# Adafruit_LC709203F_LiPoly_LiIon_Fuel_Gau.net
KiCad netlist of a schematic drawn in EAGLE
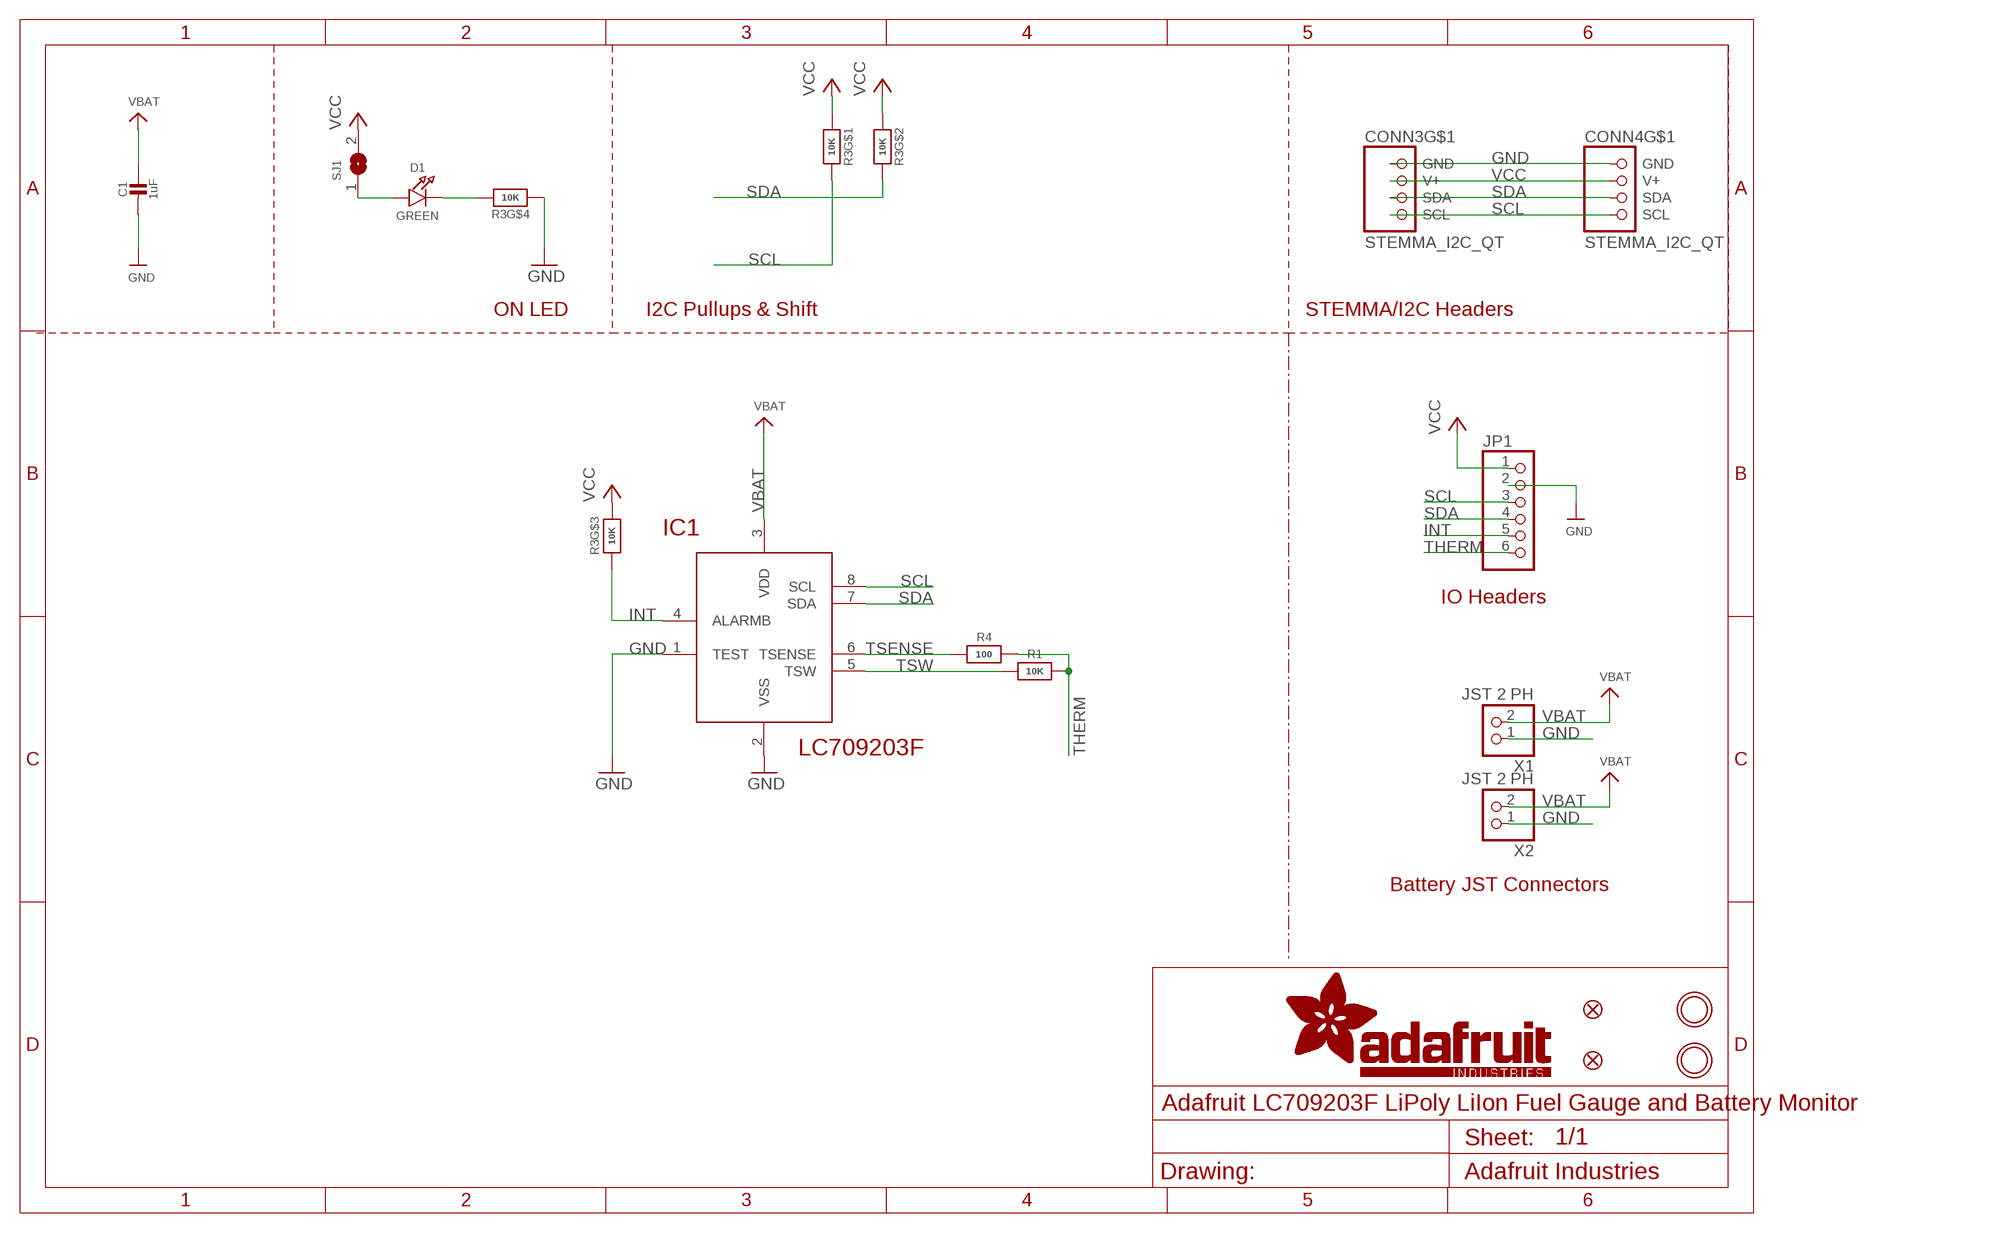
[diagram p0: schematic, sheet 1]

(export (version "E")
  (design (tool "Eeschema 10.0.6"))
  (components
    (comp (ref "C1")
      (value "1uF")
      (footprint "eagle-import:0603-NO")
      (libsource (lib "eagle-import") (part "CAP_CERAMIC0603_NO"))
    )
    (comp (ref "CONN3")
      (value "STEMMA_I2C_QT")
      (footprint "eagle-import:JST_SH4")
      (libsource (lib "eagle-import") (part "STEMMA_I2C_QT"))
    )
    (comp (ref "CONN4")
      (value "STEMMA_I2C_QT")
      (footprint "eagle-import:JST_SH4")
      (libsource (lib "eagle-import") (part "STEMMA_I2C_QT"))
    )
    (comp (ref "D1")
      (value "GREEN")
      (footprint "eagle-import:CHIPLED_0603_NOOUTLINE")
      (libsource (lib "eagle-import") (part "LED0603_NOOUTLINE"))
    )
    (comp (ref "FID3")
      (value "FIDUCIAL_1MM")
      (footprint "eagle-import:FIDUCIAL_1MM")
      (libsource (lib "eagle-import") (part "FIDUCIAL_1MM"))
    )
    (comp (ref "FID4")
      (value "FIDUCIAL_1MM")
      (footprint "eagle-import:FIDUCIAL_1MM")
      (libsource (lib "eagle-import") (part "FIDUCIAL_1MM"))
    )
    (comp (ref "IC1")
      (value "LC709203F")
      (footprint "eagle-import:WDFN8_3X4_0.65")
      (libsource (lib "eagle-import") (part "LC709203F"))
    )
    (comp (ref "JP1")
      (value "HEADER-1X670MIL")
      (footprint "eagle-import:1X06_ROUND_70")
      (libsource (lib "eagle-import") (part "HEADER-1X670MIL"))
    )
    (comp (ref "R1")
      (value "10K")
      (footprint "eagle-import:0603-NO")
      (libsource (lib "eagle-import") (part "RESISTOR_0603_NOOUT"))
    )
    (comp (ref "R3")
      (value "10K")
      (footprint "eagle-import:RESPACK_4X0603")
      (libsource (lib "eagle-import") (part "RESISTOR_4PACK"))
    )
    (comp (ref "R4")
      (value "100")
      (footprint "eagle-import:0603-NO")
      (libsource (lib "eagle-import") (part "RESISTOR_0603_NOOUT"))
    )
    (comp (ref "SJ1")
      (value "SOLDERJUMPERCLOSED")
      (footprint "eagle-import:SOLDERJUMPER_CLOSEDWIRE")
      (libsource (lib "eagle-import") (part "SOLDERJUMPERCLOSED"))
    )
    (comp (ref "U$19")
      (value "MOUNTINGHOLE2.5")
      (footprint "eagle-import:MOUNTINGHOLE_2.5_PLATED")
      (libsource (lib "eagle-import") (part "MOUNTINGHOLE2.5"))
    )
    (comp (ref "U$21")
      (value "MOUNTINGHOLE2.5")
      (footprint "eagle-import:MOUNTINGHOLE_2.5_PLATED")
      (libsource (lib "eagle-import") (part "MOUNTINGHOLE2.5"))
    )
    (comp (ref "X1")
      (value "JST 2 PH")
      (footprint "eagle-import:JSTPH2_BATT")
      (libsource (lib "eagle-import") (part "CON_JST_PH_2PIN_BATT"))
    )
    (comp (ref "X2")
      (value "JST 2 PH")
      (footprint "eagle-import:JSTPH2_BATT")
      (libsource (lib "eagle-import") (part "CON_JST_PH_2PIN_BATT"))
    )
  )
  (nets
    (net (code "1") (name "/INT") (class "Default")
      (node (ref "IC1") (pin "4") (pinfunction "ALARMB_4") (pintype "output"))
      (node (ref "JP1") (pin "5") (pinfunction "5_5") (pintype "passive"))
      (node (ref "R3") (pin "3") (pinfunction "1_3") (pintype "passive"))
    )
    (net (code "2") (name "/SCL") (class "Default")
      (node (ref "CONN3") (pin "4") (pinfunction "SCL_4") (pintype "passive"))
      (node (ref "CONN4") (pin "4") (pinfunction "SCL_4") (pintype "passive"))
      (node (ref "IC1") (pin "8") (pinfunction "SCL_8") (pintype "bidirectional"))
      (node (ref "JP1") (pin "3") (pinfunction "3_3") (pintype "passive"))
      (node (ref "R3") (pin "8") (pinfunction "2_8") (pintype "passive"))
    )
    (net (code "3") (name "/SDA") (class "Default")
      (node (ref "CONN3") (pin "3") (pinfunction "SDA_3") (pintype "passive"))
      (node (ref "CONN4") (pin "3") (pinfunction "SDA_3") (pintype "passive"))
      (node (ref "IC1") (pin "7") (pinfunction "SDA_7") (pintype "bidirectional"))
      (node (ref "JP1") (pin "4") (pinfunction "4_4") (pintype "passive"))
      (node (ref "R3") (pin "7") (pinfunction "2_7") (pintype "passive"))
    )
    (net (code "4") (name "/THERM") (class "Default")
      (node (ref "JP1") (pin "6") (pinfunction "6_6") (pintype "passive"))
      (node (ref "R1") (pin "2") (pinfunction "2_2") (pintype "passive"))
      (node (ref "R4") (pin "2") (pinfunction "2_2") (pintype "passive"))
    )
    (net (code "5") (name "/TSENSE") (class "Default")
      (node (ref "IC1") (pin "6") (pinfunction "TSENSE_6") (pintype "power_in"))
      (node (ref "R4") (pin "1") (pinfunction "1_1") (pintype "passive"))
    )
    (net (code "6") (name "/TSW") (class "Default")
      (node (ref "IC1") (pin "5") (pinfunction "TSW_5") (pintype "input"))
      (node (ref "R1") (pin "1") (pinfunction "1_1") (pintype "passive"))
    )
    (net (code "7") (name "GND") (class "Default")
      (node (ref "C1") (pin "2") (pinfunction "2_2") (pintype "passive"))
      (node (ref "CONN3") (pin "1") (pinfunction "GND_1") (pintype "passive"))
      (node (ref "CONN4") (pin "1") (pinfunction "GND_1") (pintype "passive"))
      (node (ref "IC1") (pin "1") (pinfunction "TEST_1") (pintype "bidirectional"))
      (node (ref "IC1") (pin "2") (pinfunction "VSS_2") (pintype "power_in"))
      (node (ref "JP1") (pin "2") (pinfunction "2_2") (pintype "passive"))
      (node (ref "R3") (pin "4") (pinfunction "1_4") (pintype "passive"))
      (node (ref "X1") (pin "1") (pinfunction "1_1") (pintype "passive"))
      (node (ref "X2") (pin "1") (pinfunction "1_1") (pintype "passive"))
    )
    (net (code "8") (name "Net-(D1-PadA)") (class "Default")
      (node (ref "D1") (pin "A") (pinfunction "A_A") (pintype "passive"))
      (node (ref "SJ1") (pin "1") (pinfunction "1_1") (pintype "passive"))
    )
    (net (code "9") (name "Net-(R3D-2)") (class "Default")
      (node (ref "D1") (pin "C") (pinfunction "C_C") (pintype "passive"))
      (node (ref "R3") (pin "5") (pinfunction "2_5") (pintype "passive"))
    )
    (net (code "10") (name "VBAT") (class "Default")
      (node (ref "C1") (pin "1") (pinfunction "1_1") (pintype "passive"))
      (node (ref "IC1") (pin "3") (pinfunction "VDD_3") (pintype "power_in"))
      (node (ref "X1") (pin "2") (pinfunction "2_2") (pintype "passive"))
      (node (ref "X2") (pin "2") (pinfunction "2_2") (pintype "passive"))
    )
    (net (code "11") (name "VCC") (class "Default")
      (node (ref "CONN3") (pin "2") (pinfunction "V+_2") (pintype "passive"))
      (node (ref "CONN4") (pin "2") (pinfunction "V+_2") (pintype "passive"))
      (node (ref "JP1") (pin "1") (pinfunction "1_1") (pintype "passive"))
      (node (ref "R3") (pin "1") (pinfunction "1_1") (pintype "passive"))
      (node (ref "R3") (pin "2") (pinfunction "1_2") (pintype "passive"))
      (node (ref "R3") (pin "6") (pinfunction "2_6") (pintype "passive"))
      (node (ref "SJ1") (pin "2") (pinfunction "2_2") (pintype "passive"))
    )
  )
)
